# Sheet1.net
KiCad netlist of a schematic drawn in Altium Designer
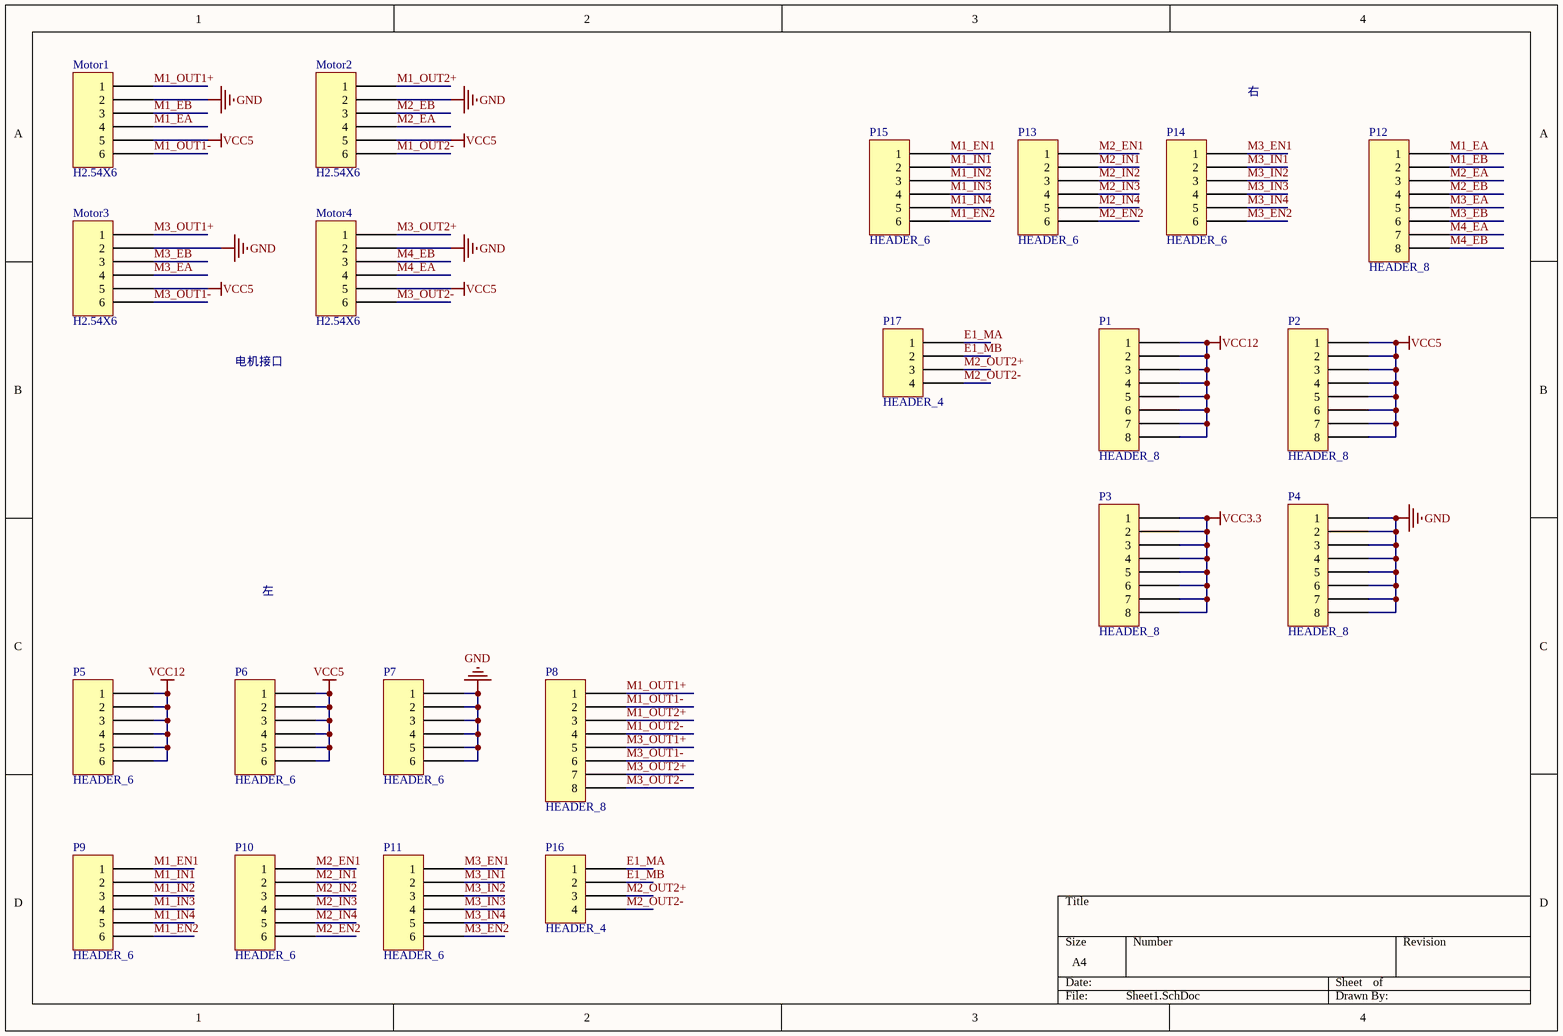
[diagram p0: Sheet1.SchDoc]

(export (version "E")
  (design (tool "Eeschema 10.0.6"))
  (components
    (comp (ref "Motor1") (value "H2.54X6") (footprint "Header6") (libsource (lib "Schlib1") (part "H2.54X6")))
    (comp (ref "Motor2") (value "H2.54X6") (footprint "Header6") (libsource (lib "Schlib1") (part "H2.54X6")))
    (comp (ref "Motor3") (value "H2.54X6") (footprint "Header6") (libsource (lib "Schlib1") (part "H2.54X6")))
    (comp (ref "Motor4") (value "H2.54X6") (footprint "Header6") (libsource (lib "Schlib1") (part "H2.54X6")))
    (comp (ref "P1") (value "HEADER_8") (footprint "HDR1X8") (libsource (lib "Schlib1") (part "HEADER_8")))
    (comp (ref "P2") (value "HEADER_8") (footprint "HDR1X8") (libsource (lib "Schlib1") (part "HEADER_8")))
    (comp (ref "P3") (value "HEADER_8") (footprint "HDR1X8") (libsource (lib "Schlib1") (part "HEADER_8")))
    (comp (ref "P4") (value "HEADER_8") (footprint "HDR1X8") (libsource (lib "Schlib1") (part "HEADER_8")))
    (comp (ref "P5") (value "HEADER_6") (footprint "HDR1X6") (libsource (lib "Schlib1") (part "HEADER_6")))
    (comp (ref "P6") (value "HEADER_6") (footprint "HDR1X6") (libsource (lib "Schlib1") (part "HEADER_6")))
    (comp (ref "P7") (value "HEADER_6") (footprint "HDR1X6") (libsource (lib "Schlib1") (part "HEADER_6")))
    (comp (ref "P8") (value "HEADER_8") (footprint "HDR1X8") (libsource (lib "Schlib1") (part "HEADER_8")))
    (comp (ref "P9") (value "HEADER_6") (footprint "HDR1X6") (libsource (lib "Schlib1") (part "HEADER_6")))
    (comp (ref "P10") (value "HEADER_6") (footprint "HDR1X6") (libsource (lib "Schlib1") (part "HEADER_6")))
    (comp (ref "P11") (value "HEADER_6") (footprint "HDR1X6") (libsource (lib "Schlib1") (part "HEADER_6")))
    (comp (ref "P12") (value "HEADER_8") (footprint "HDR1X8") (libsource (lib "Schlib1") (part "HEADER_8")))
    (comp (ref "P13") (value "HEADER_6") (footprint "HDR1X6") (libsource (lib "Schlib1") (part "HEADER_6")))
    (comp (ref "P14") (value "HEADER_6") (footprint "HDR1X6") (libsource (lib "Schlib1") (part "HEADER_6")))
    (comp (ref "P15") (value "HEADER_6") (footprint "HDR1X6") (libsource (lib "Schlib1") (part "HEADER_6")))
    (comp (ref "P16") (value "HEADER_4") (footprint "HDR1X4") (libsource (lib "Schlib1") (part "HEADER_4")))
    (comp (ref "P17") (value "HEADER_4") (footprint "HDR1X4") (libsource (lib "Schlib1") (part "HEADER_4")))
  )
  (nets
    (net (code "1") (name "/E1_MA") (class "Default")
      (node (ref "P16") (pin "1") (pinfunction "1_1") (pintype "passive"))
      (node (ref "P17") (pin "1") (pinfunction "1_1") (pintype "passive"))
    )
    (net (code "2") (name "/E1_MB") (class "Default")
      (node (ref "P16") (pin "2") (pinfunction "2_2") (pintype "passive"))
      (node (ref "P17") (pin "2") (pinfunction "2_2") (pintype "passive"))
    )
    (net (code "3") (name "/M1_EA") (class "Default")
      (node (ref "Motor1") (pin "4") (pinfunction "4_4") (pintype "passive"))
      (node (ref "P12") (pin "1") (pinfunction "1_1") (pintype "passive"))
    )
    (net (code "4") (name "/M1_EB") (class "Default")
      (node (ref "Motor1") (pin "3") (pinfunction "3_3") (pintype "passive"))
      (node (ref "P12") (pin "2") (pinfunction "2_2") (pintype "passive"))
    )
    (net (code "5") (name "/M1_EN1") (class "Default")
      (node (ref "P15") (pin "1") (pinfunction "1_1") (pintype "passive"))
      (node (ref "P9") (pin "1") (pinfunction "1_1") (pintype "passive"))
    )
    (net (code "6") (name "/M1_EN2") (class "Default")
      (node (ref "P15") (pin "6") (pinfunction "6_6") (pintype "passive"))
      (node (ref "P9") (pin "6") (pinfunction "6_6") (pintype "passive"))
    )
    (net (code "7") (name "/M1_IN1") (class "Default")
      (node (ref "P15") (pin "2") (pinfunction "2_2") (pintype "passive"))
      (node (ref "P9") (pin "2") (pinfunction "2_2") (pintype "passive"))
    )
    (net (code "8") (name "/M1_IN2") (class "Default")
      (node (ref "P15") (pin "3") (pinfunction "3_3") (pintype "passive"))
      (node (ref "P9") (pin "3") (pinfunction "3_3") (pintype "passive"))
    )
    (net (code "9") (name "/M1_IN3") (class "Default")
      (node (ref "P15") (pin "4") (pinfunction "4_4") (pintype "passive"))
      (node (ref "P9") (pin "4") (pinfunction "4_4") (pintype "passive"))
    )
    (net (code "10") (name "/M1_IN4") (class "Default")
      (node (ref "P15") (pin "5") (pinfunction "5_5") (pintype "passive"))
      (node (ref "P9") (pin "5") (pinfunction "5_5") (pintype "passive"))
    )
    (net (code "11") (name "/M1_OUT1+") (class "Default")
      (node (ref "Motor1") (pin "1") (pinfunction "1_1") (pintype "passive"))
      (node (ref "P8") (pin "1") (pinfunction "1_1") (pintype "passive"))
    )
    (net (code "12") (name "/M1_OUT1-") (class "Default")
      (node (ref "Motor1") (pin "6") (pinfunction "6_6") (pintype "passive"))
      (node (ref "P8") (pin "2") (pinfunction "2_2") (pintype "passive"))
    )
    (net (code "13") (name "/M1_OUT2+") (class "Default")
      (node (ref "Motor2") (pin "1") (pinfunction "1_1") (pintype "passive"))
      (node (ref "P8") (pin "3") (pinfunction "3_3") (pintype "passive"))
    )
    (net (code "14") (name "/M1_OUT2-") (class "Default")
      (node (ref "Motor2") (pin "6") (pinfunction "6_6") (pintype "passive"))
      (node (ref "P8") (pin "4") (pinfunction "4_4") (pintype "passive"))
    )
    (net (code "15") (name "/M2_EA") (class "Default")
      (node (ref "Motor2") (pin "4") (pinfunction "4_4") (pintype "passive"))
      (node (ref "P12") (pin "3") (pinfunction "3_3") (pintype "passive"))
    )
    (net (code "16") (name "/M2_EB") (class "Default")
      (node (ref "Motor2") (pin "3") (pinfunction "3_3") (pintype "passive"))
      (node (ref "P12") (pin "4") (pinfunction "4_4") (pintype "passive"))
    )
    (net (code "17") (name "/M2_EN1") (class "Default")
      (node (ref "P10") (pin "1") (pinfunction "1_1") (pintype "passive"))
      (node (ref "P13") (pin "1") (pinfunction "1_1") (pintype "passive"))
    )
    (net (code "18") (name "/M2_EN2") (class "Default")
      (node (ref "P10") (pin "6") (pinfunction "6_6") (pintype "passive"))
      (node (ref "P13") (pin "6") (pinfunction "6_6") (pintype "passive"))
    )
    (net (code "19") (name "/M2_IN1") (class "Default")
      (node (ref "P10") (pin "2") (pinfunction "2_2") (pintype "passive"))
      (node (ref "P13") (pin "2") (pinfunction "2_2") (pintype "passive"))
    )
    (net (code "20") (name "/M2_IN2") (class "Default")
      (node (ref "P10") (pin "3") (pinfunction "3_3") (pintype "passive"))
      (node (ref "P13") (pin "3") (pinfunction "3_3") (pintype "passive"))
    )
    (net (code "21") (name "/M2_IN3") (class "Default")
      (node (ref "P10") (pin "4") (pinfunction "4_4") (pintype "passive"))
      (node (ref "P13") (pin "4") (pinfunction "4_4") (pintype "passive"))
    )
    (net (code "22") (name "/M2_IN4") (class "Default")
      (node (ref "P10") (pin "5") (pinfunction "5_5") (pintype "passive"))
      (node (ref "P13") (pin "5") (pinfunction "5_5") (pintype "passive"))
    )
    (net (code "23") (name "/M2_OUT2+") (class "Default")
      (node (ref "P16") (pin "3") (pinfunction "3_3") (pintype "passive"))
      (node (ref "P17") (pin "3") (pinfunction "3_3") (pintype "passive"))
    )
    (net (code "24") (name "/M2_OUT2-") (class "Default")
      (node (ref "P16") (pin "4") (pinfunction "4_4") (pintype "passive"))
      (node (ref "P17") (pin "4") (pinfunction "4_4") (pintype "passive"))
    )
    (net (code "25") (name "/M3_EA") (class "Default")
      (node (ref "Motor3") (pin "4") (pinfunction "4_4") (pintype "passive"))
      (node (ref "P12") (pin "5") (pinfunction "5_5") (pintype "passive"))
    )
    (net (code "26") (name "/M3_EB") (class "Default")
      (node (ref "Motor3") (pin "3") (pinfunction "3_3") (pintype "passive"))
      (node (ref "P12") (pin "6") (pinfunction "6_6") (pintype "passive"))
    )
    (net (code "27") (name "/M3_EN1") (class "Default")
      (node (ref "P11") (pin "1") (pinfunction "1_1") (pintype "passive"))
      (node (ref "P14") (pin "1") (pinfunction "1_1") (pintype "passive"))
    )
    (net (code "28") (name "/M3_EN2") (class "Default")
      (node (ref "P11") (pin "6") (pinfunction "6_6") (pintype "passive"))
      (node (ref "P14") (pin "6") (pinfunction "6_6") (pintype "passive"))
    )
    (net (code "29") (name "/M3_IN1") (class "Default")
      (node (ref "P11") (pin "2") (pinfunction "2_2") (pintype "passive"))
      (node (ref "P14") (pin "2") (pinfunction "2_2") (pintype "passive"))
    )
    (net (code "30") (name "/M3_IN2") (class "Default")
      (node (ref "P11") (pin "3") (pinfunction "3_3") (pintype "passive"))
      (node (ref "P14") (pin "3") (pinfunction "3_3") (pintype "passive"))
    )
    (net (code "31") (name "/M3_IN3") (class "Default")
      (node (ref "P11") (pin "4") (pinfunction "4_4") (pintype "passive"))
      (node (ref "P14") (pin "4") (pinfunction "4_4") (pintype "passive"))
    )
    (net (code "32") (name "/M3_IN4") (class "Default")
      (node (ref "P11") (pin "5") (pinfunction "5_5") (pintype "passive"))
      (node (ref "P14") (pin "5") (pinfunction "5_5") (pintype "passive"))
    )
    (net (code "33") (name "/M3_OUT1+") (class "Default")
      (node (ref "Motor3") (pin "1") (pinfunction "1_1") (pintype "passive"))
      (node (ref "P8") (pin "5") (pinfunction "5_5") (pintype "passive"))
    )
    (net (code "34") (name "/M3_OUT1-") (class "Default")
      (node (ref "Motor3") (pin "6") (pinfunction "6_6") (pintype "passive"))
      (node (ref "P8") (pin "6") (pinfunction "6_6") (pintype "passive"))
    )
    (net (code "35") (name "/M3_OUT2+") (class "Default")
      (node (ref "Motor4") (pin "1") (pinfunction "1_1") (pintype "passive"))
      (node (ref "P8") (pin "7") (pinfunction "7_7") (pintype "passive"))
    )
    (net (code "36") (name "/M3_OUT2-") (class "Default")
      (node (ref "Motor4") (pin "6") (pinfunction "6_6") (pintype "passive"))
      (node (ref "P8") (pin "8") (pinfunction "8_8") (pintype "passive"))
    )
    (net (code "37") (name "/M4_EA") (class "Default")
      (node (ref "Motor4") (pin "4") (pinfunction "4_4") (pintype "passive"))
      (node (ref "P12") (pin "7") (pinfunction "7_7") (pintype "passive"))
    )
    (net (code "38") (name "/M4_EB") (class "Default")
      (node (ref "Motor4") (pin "3") (pinfunction "3_3") (pintype "passive"))
      (node (ref "P12") (pin "8") (pinfunction "8_8") (pintype "passive"))
    )
    (net (code "39") (name "GND") (class "Default")
      (node (ref "Motor1") (pin "2") (pinfunction "2_2") (pintype "passive"))
      (node (ref "Motor2") (pin "2") (pinfunction "2_2") (pintype "passive"))
      (node (ref "Motor3") (pin "2") (pinfunction "2_2") (pintype "passive"))
      (node (ref "Motor4") (pin "2") (pinfunction "2_2") (pintype "passive"))
      (node (ref "P4") (pin "1") (pinfunction "1_1") (pintype "passive"))
      (node (ref "P4") (pin "2") (pinfunction "2_2") (pintype "passive"))
      (node (ref "P4") (pin "3") (pinfunction "3_3") (pintype "passive"))
      (node (ref "P4") (pin "4") (pinfunction "4_4") (pintype "passive"))
      (node (ref "P4") (pin "5") (pinfunction "5_5") (pintype "passive"))
      (node (ref "P4") (pin "6") (pinfunction "6_6") (pintype "passive"))
      (node (ref "P4") (pin "7") (pinfunction "7_7") (pintype "passive"))
      (node (ref "P4") (pin "8") (pinfunction "8_8") (pintype "passive"))
      (node (ref "P7") (pin "1") (pinfunction "1_1") (pintype "passive"))
      (node (ref "P7") (pin "2") (pinfunction "2_2") (pintype "passive"))
      (node (ref "P7") (pin "3") (pinfunction "3_3") (pintype "passive"))
      (node (ref "P7") (pin "4") (pinfunction "4_4") (pintype "passive"))
      (node (ref "P7") (pin "5") (pinfunction "5_5") (pintype "passive"))
      (node (ref "P7") (pin "6") (pinfunction "6_6") (pintype "passive"))
    )
    (net (code "40") (name "VCC3.3") (class "Default")
      (node (ref "P3") (pin "1") (pinfunction "1_1") (pintype "passive"))
      (node (ref "P3") (pin "2") (pinfunction "2_2") (pintype "passive"))
      (node (ref "P3") (pin "3") (pinfunction "3_3") (pintype "passive"))
      (node (ref "P3") (pin "4") (pinfunction "4_4") (pintype "passive"))
      (node (ref "P3") (pin "5") (pinfunction "5_5") (pintype "passive"))
      (node (ref "P3") (pin "6") (pinfunction "6_6") (pintype "passive"))
      (node (ref "P3") (pin "7") (pinfunction "7_7") (pintype "passive"))
      (node (ref "P3") (pin "8") (pinfunction "8_8") (pintype "passive"))
    )
    (net (code "41") (name "VCC5") (class "Default")
      (node (ref "Motor1") (pin "5") (pinfunction "5_5") (pintype "passive"))
      (node (ref "Motor2") (pin "5") (pinfunction "5_5") (pintype "passive"))
      (node (ref "Motor3") (pin "5") (pinfunction "5_5") (pintype "passive"))
      (node (ref "Motor4") (pin "5") (pinfunction "5_5") (pintype "passive"))
      (node (ref "P2") (pin "1") (pinfunction "1_1") (pintype "passive"))
      (node (ref "P2") (pin "2") (pinfunction "2_2") (pintype "passive"))
      (node (ref "P2") (pin "3") (pinfunction "3_3") (pintype "passive"))
      (node (ref "P2") (pin "4") (pinfunction "4_4") (pintype "passive"))
      (node (ref "P2") (pin "5") (pinfunction "5_5") (pintype "passive"))
      (node (ref "P2") (pin "6") (pinfunction "6_6") (pintype "passive"))
      (node (ref "P2") (pin "7") (pinfunction "7_7") (pintype "passive"))
      (node (ref "P2") (pin "8") (pinfunction "8_8") (pintype "passive"))
      (node (ref "P6") (pin "1") (pinfunction "1_1") (pintype "passive"))
      (node (ref "P6") (pin "2") (pinfunction "2_2") (pintype "passive"))
      (node (ref "P6") (pin "3") (pinfunction "3_3") (pintype "passive"))
      (node (ref "P6") (pin "4") (pinfunction "4_4") (pintype "passive"))
      (node (ref "P6") (pin "5") (pinfunction "5_5") (pintype "passive"))
      (node (ref "P6") (pin "6") (pinfunction "6_6") (pintype "passive"))
    )
    (net (code "42") (name "VCC12") (class "Default")
      (node (ref "P1") (pin "1") (pinfunction "1_1") (pintype "passive"))
      (node (ref "P1") (pin "2") (pinfunction "2_2") (pintype "passive"))
      (node (ref "P1") (pin "3") (pinfunction "3_3") (pintype "passive"))
      (node (ref "P1") (pin "4") (pinfunction "4_4") (pintype "passive"))
      (node (ref "P1") (pin "5") (pinfunction "5_5") (pintype "passive"))
      (node (ref "P1") (pin "6") (pinfunction "6_6") (pintype "passive"))
      (node (ref "P1") (pin "7") (pinfunction "7_7") (pintype "passive"))
      (node (ref "P1") (pin "8") (pinfunction "8_8") (pintype "passive"))
      (node (ref "P5") (pin "1") (pinfunction "1_1") (pintype "passive"))
      (node (ref "P5") (pin "2") (pinfunction "2_2") (pintype "passive"))
      (node (ref "P5") (pin "3") (pinfunction "3_3") (pintype "passive"))
      (node (ref "P5") (pin "4") (pinfunction "4_4") (pintype "passive"))
      (node (ref "P5") (pin "5") (pinfunction "5_5") (pintype "passive"))
      (node (ref "P5") (pin "6") (pinfunction "6_6") (pintype "passive"))
    )
  )
)
